# EagleSchematicv7.net
KiCad netlist of a schematic drawn in EAGLE
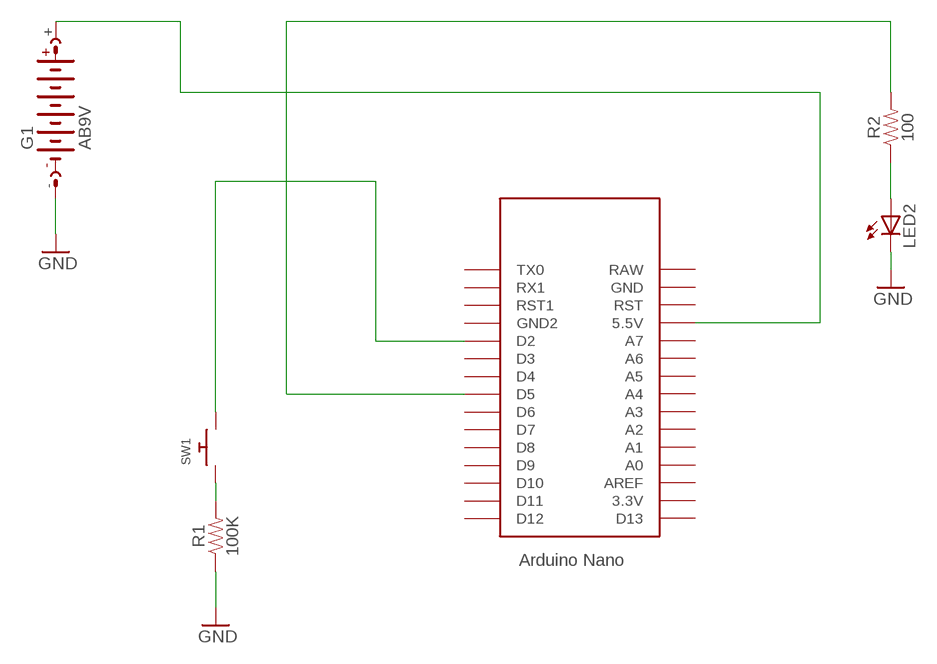
[diagram p0: schematic, sheet 1]

(export (version "E")
  (design (tool "Eeschema 10.0.6"))
  (components
    (comp (ref "G1")
      (value "AB9V")
      (footprint "eagle-import:AB9V")
      (libsource (lib "eagle-import") (part "AB9V"))
    )
    (comp (ref "LED2")
      (value "LED5MM")
      (footprint "eagle-import:LED5MM")
      (libsource (lib "eagle-import") (part "LED5MM"))
    )
    (comp (ref "R1")
      (value "100K")
      (footprint "eagle-import:0402")
      (libsource (lib "eagle-import") (part "100KOHM-0402-1/16W-1%"))
    )
    (comp (ref "R2")
      (value "100")
      (footprint "eagle-import:0603")
      (libsource (lib "eagle-import") (part "100OHM-0603-1/4W-5%"))
    )
    (comp (ref "SW1")
      (value "SWITCH_PUSHBUTTONSOFTTOUCHSMD_SJ")
      (footprint "eagle-import:PUSHBUTTON_SMD_SJ")
      (libsource (lib "eagle-import") (part "SWITCH_PUSHBUTTONSOFTTOUCHSMD_SJ"))
    )
    (comp (ref "U$1")
      (value "NANO")
      (footprint "eagle-import:NANO")
      (libsource (lib "eagle-import") (part "NANO"))
    )
  )
  (nets
    (net (code "1") (name "GND") (class "Default")
      (node (ref "G1") (pin "-") (pinfunction "-_-") (pintype "passive"))
      (node (ref "LED2") (pin "K") (pinfunction "C_K") (pintype "passive"))
      (node (ref "R1") (pin "1") (pinfunction "1_1") (pintype "passive"))
    )
    (net (code "2") (name "Net-(LED2-PadA)") (class "Default")
      (node (ref "LED2") (pin "A") (pinfunction "A_A") (pintype "passive"))
      (node (ref "R2") (pin "1") (pinfunction "1_1") (pintype "passive"))
    )
    (net (code "3") (name "Net-(R1-Pad2)") (class "Default")
      (node (ref "R1") (pin "2") (pinfunction "2_2") (pintype "passive"))
      (node (ref "SW1") (pin "P$1") (pinfunction "P$1_P$1") (pintype "passive"))
    )
    (net (code "4") (name "Net-(R2-Pad2)") (class "Default")
      (node (ref "R2") (pin "2") (pinfunction "2_2") (pintype "passive"))
      (node (ref "U$1") (pin "D5") (pinfunction "D5_D5") (pintype "bidirectional"))
    )
    (net (code "5") (name "Net-(SW1-PadP$2)") (class "Default")
      (node (ref "SW1") (pin "P$2") (pinfunction "P$2_P$2") (pintype "passive"))
      (node (ref "U$1") (pin "D2") (pinfunction "D2_D2") (pintype "bidirectional"))
    )
    (net (code "6") (name "Net-(U$1-5.5V)") (class "Default")
      (node (ref "G1") (pin "+") (pinfunction "+_+") (pintype "passive"))
      (node (ref "U$1") (pin "5V") (pinfunction "5.5V_5V") (pintype "bidirectional"))
    )
    (net (code "7") (name "unconnected-(U$1-GND2-PadGND1)") (class "Default")
      (node (ref "U$1") (pin "GND1") (pinfunction "GND2_GND1") (pintype "bidirectional"))
    )
    (net (code "8") (name "unconnected-(U$1-Pad3.3V)") (class "Default")
      (node (ref "U$1") (pin "3.3V") (pinfunction "3.3V_3.3V") (pintype "bidirectional"))
    )
    (net (code "9") (name "unconnected-(U$1-PadA0)") (class "Default")
      (node (ref "U$1") (pin "A0") (pinfunction "A0_A0") (pintype "bidirectional"))
    )
    (net (code "10") (name "unconnected-(U$1-PadA1)") (class "Default")
      (node (ref "U$1") (pin "A1") (pinfunction "A1_A1") (pintype "bidirectional"))
    )
    (net (code "11") (name "unconnected-(U$1-PadA2)") (class "Default")
      (node (ref "U$1") (pin "A2") (pinfunction "A2_A2") (pintype "bidirectional"))
    )
    (net (code "12") (name "unconnected-(U$1-PadA3)") (class "Default")
      (node (ref "U$1") (pin "A3") (pinfunction "A3_A3") (pintype "bidirectional"))
    )
    (net (code "13") (name "unconnected-(U$1-PadA4)") (class "Default")
      (node (ref "U$1") (pin "A4") (pinfunction "A4_A4") (pintype "bidirectional"))
    )
    (net (code "14") (name "unconnected-(U$1-PadA5)") (class "Default")
      (node (ref "U$1") (pin "A5") (pinfunction "A5_A5") (pintype "bidirectional"))
    )
    (net (code "15") (name "unconnected-(U$1-PadA6)") (class "Default")
      (node (ref "U$1") (pin "A6") (pinfunction "A6_A6") (pintype "bidirectional"))
    )
    (net (code "16") (name "unconnected-(U$1-PadA7)") (class "Default")
      (node (ref "U$1") (pin "A7") (pinfunction "A7_A7") (pintype "bidirectional"))
    )
    (net (code "17") (name "unconnected-(U$1-PadAREF)") (class "Default")
      (node (ref "U$1") (pin "AREF") (pinfunction "AREF_AREF") (pintype "bidirectional"))
    )
    (net (code "18") (name "unconnected-(U$1-PadD3)") (class "Default")
      (node (ref "U$1") (pin "D3") (pinfunction "D3_D3") (pintype "bidirectional"))
    )
    (net (code "19") (name "unconnected-(U$1-PadD4)") (class "Default")
      (node (ref "U$1") (pin "D4") (pinfunction "D4_D4") (pintype "bidirectional"))
    )
    (net (code "20") (name "unconnected-(U$1-PadD6)") (class "Default")
      (node (ref "U$1") (pin "D6") (pinfunction "D6_D6") (pintype "bidirectional"))
    )
    (net (code "21") (name "unconnected-(U$1-PadD7)") (class "Default")
      (node (ref "U$1") (pin "D7") (pinfunction "D7_D7") (pintype "bidirectional"))
    )
    (net (code "22") (name "unconnected-(U$1-PadD8)") (class "Default")
      (node (ref "U$1") (pin "D8") (pinfunction "D8_D8") (pintype "bidirectional"))
    )
    (net (code "23") (name "unconnected-(U$1-PadD9)") (class "Default")
      (node (ref "U$1") (pin "D9") (pinfunction "D9_D9") (pintype "bidirectional"))
    )
    (net (code "24") (name "unconnected-(U$1-PadD10)") (class "Default")
      (node (ref "U$1") (pin "D10") (pinfunction "D10_D10") (pintype "bidirectional"))
    )
    (net (code "25") (name "unconnected-(U$1-PadD11)") (class "Default")
      (node (ref "U$1") (pin "D11") (pinfunction "D11_D11") (pintype "bidirectional"))
    )
    (net (code "26") (name "unconnected-(U$1-PadD12)") (class "Default")
      (node (ref "U$1") (pin "D12") (pinfunction "D12_D12") (pintype "bidirectional"))
    )
    (net (code "27") (name "unconnected-(U$1-PadD13)") (class "Default")
      (node (ref "U$1") (pin "D13") (pinfunction "D13_D13") (pintype "bidirectional"))
    )
    (net (code "28") (name "unconnected-(U$1-PadGND)") (class "Default")
      (node (ref "U$1") (pin "GND") (pinfunction "GND_GND") (pintype "bidirectional"))
    )
    (net (code "29") (name "unconnected-(U$1-PadICSP1)") (class "Default")
      (node (ref "U$1") (pin "ICSP1") (pinfunction "ICSP1_ICSP1") (pintype "bidirectional"))
    )
    (net (code "30") (name "unconnected-(U$1-PadICSP2)") (class "Default")
      (node (ref "U$1") (pin "ICSP2") (pinfunction "ICSP2_ICSP2") (pintype "bidirectional"))
    )
    (net (code "31") (name "unconnected-(U$1-PadICSP3)") (class "Default")
      (node (ref "U$1") (pin "ICSP3") (pinfunction "ICSP3_ICSP3") (pintype "bidirectional"))
    )
    (net (code "32") (name "unconnected-(U$1-PadICSP4)") (class "Default")
      (node (ref "U$1") (pin "ICSP4") (pinfunction "ICSP4_ICSP4") (pintype "bidirectional"))
    )
    (net (code "33") (name "unconnected-(U$1-PadICSP5)") (class "Default")
      (node (ref "U$1") (pin "ICSP5") (pinfunction "ICSP5_ICSP5") (pintype "bidirectional"))
    )
    (net (code "34") (name "unconnected-(U$1-PadICSP6)") (class "Default")
      (node (ref "U$1") (pin "ICSP6") (pinfunction "ICSP6_ICSP6") (pintype "bidirectional"))
    )
    (net (code "35") (name "unconnected-(U$1-PadRAW)") (class "Default")
      (node (ref "U$1") (pin "RAW") (pinfunction "RAW_RAW") (pintype "bidirectional"))
    )
    (net (code "36") (name "unconnected-(U$1-PadRST)") (class "Default")
      (node (ref "U$1") (pin "RST") (pinfunction "RST_RST") (pintype "bidirectional"))
    )
    (net (code "37") (name "unconnected-(U$1-PadRST1)") (class "Default")
      (node (ref "U$1") (pin "RST1") (pinfunction "RST1_RST1") (pintype "bidirectional"))
    )
    (net (code "38") (name "unconnected-(U$1-PadRX1)") (class "Default")
      (node (ref "U$1") (pin "RX1") (pinfunction "RX1_RX1") (pintype "bidirectional"))
    )
    (net (code "39") (name "unconnected-(U$1-PadTX0)") (class "Default")
      (node (ref "U$1") (pin "TX0") (pinfunction "TX0_TX0") (pintype "bidirectional"))
    )
  )
)
